# Led.net
KiCad netlist of a schematic drawn in Altium Designer
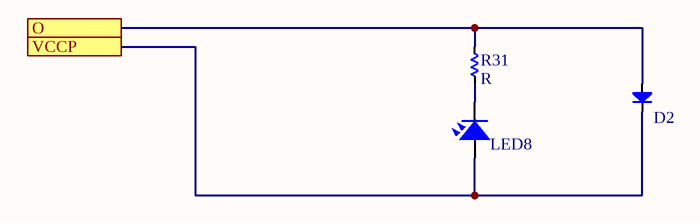
[diagram p0: Led.SchDoc]

(export (version "E")
  (design (tool "Eeschema 10.0.6"))
  (components
    (comp (ref "D2")
      (value "Diode")
      (footprint "DIO-SMD-123")
      (description "Default Diode")
      (fields (field (name "PUBLISHER") "Altium Limited"))
      (libsource (lib "nhan") (part "Diode"))
    )
    (comp (ref "LED8")
      (value "LED")
      (footprint "LED-0805-Blue")
      (libsource (lib "BanLinhKien") (part "LED SMD"))
    )
    (comp (ref "R31") (value "R") (footprint "RES-SMD-0603_BIG") (libsource (lib "nhan") (part "R")))
  )
  (nets
    (net (code "1") (name "/O") (class "Default")
      (node (ref "D2") (pin "1") (pinfunction "A_1") (pintype "passive"))
      (node (ref "R31") (pin "1") (pinfunction "1_1") (pintype "passive"))
    )
    (net (code "2") (name "/VCCP") (class "Default")
      (node (ref "D2") (pin "2") (pinfunction "K_2") (pintype "passive"))
      (node (ref "LED8") (pin "1") (pinfunction "1_1") (pintype "passive"))
    )
    (net (code "3") (name "Net-(LED8-Pad2)") (class "Default")
      (node (ref "LED8") (pin "2") (pinfunction "2_2") (pintype "passive"))
      (node (ref "R31") (pin "2") (pinfunction "2_2") (pintype "passive"))
    )
  )
)
